# Signal_Relay_Switch.net
KiCad netlist of a schematic drawn in EasyEDA Pro
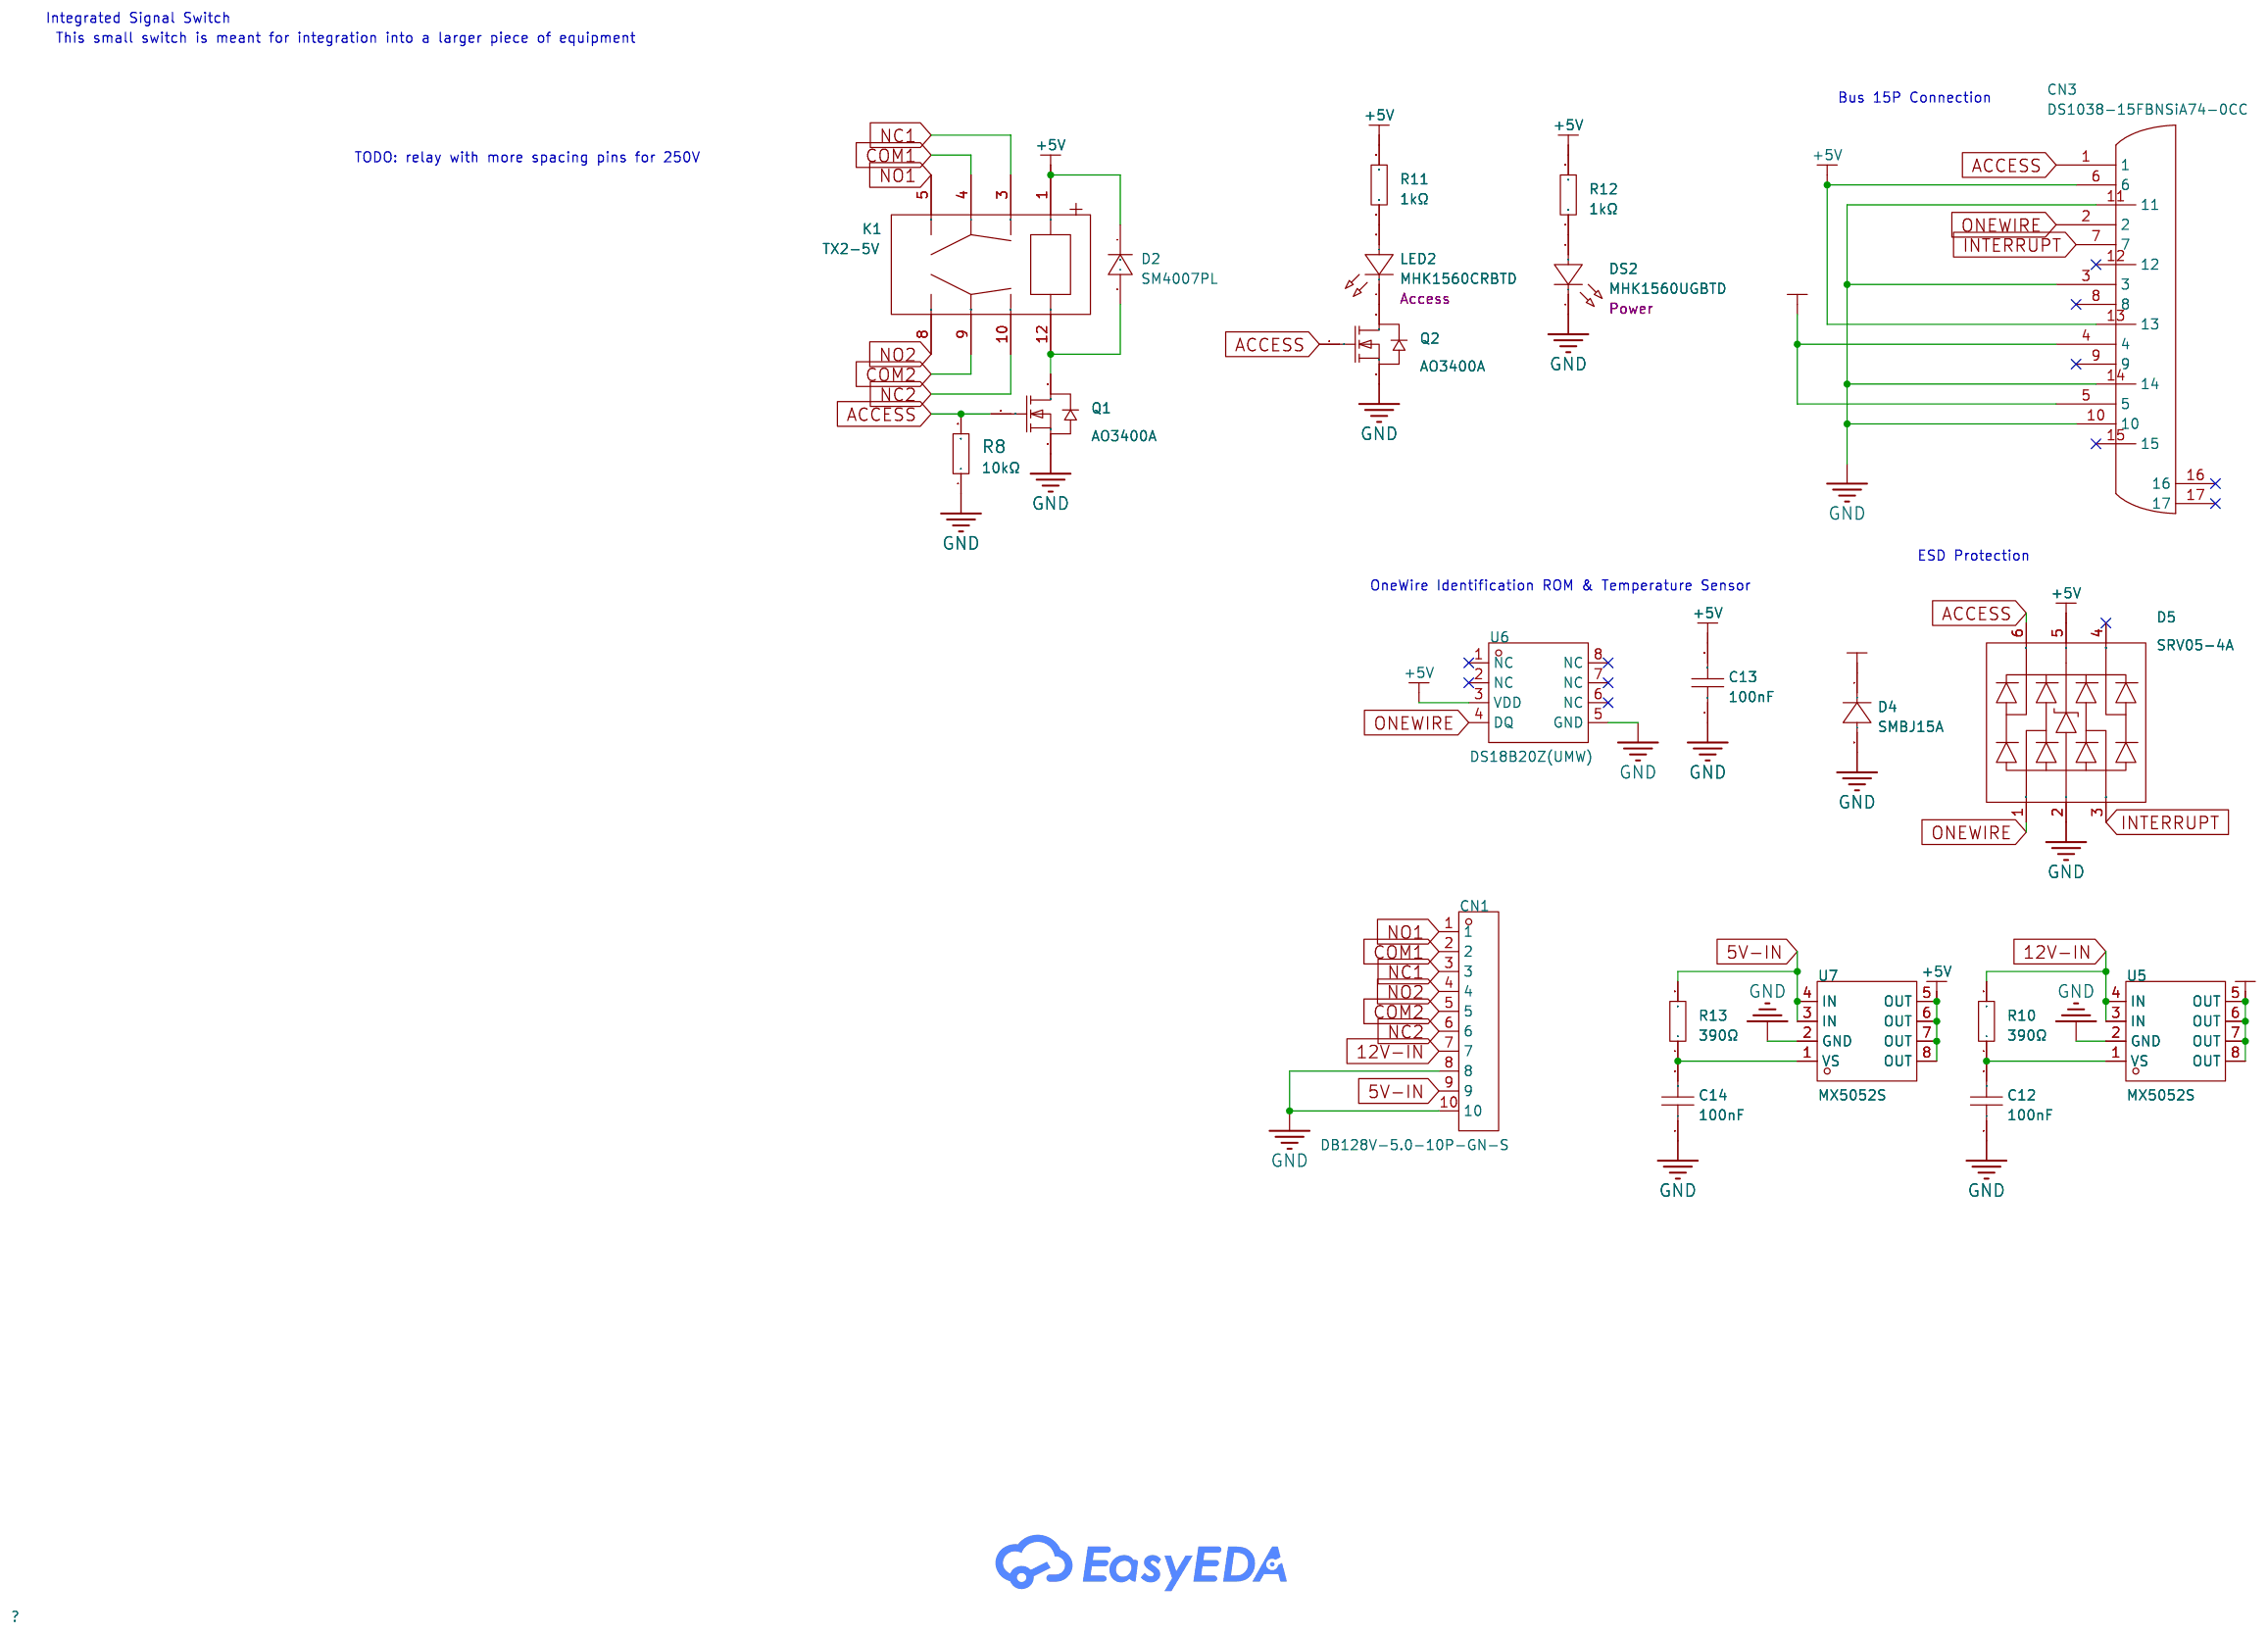
[diagram p0: schematic sheet]

(export (version "E")
  (design (tool "Eeschema 10.0.6"))
  (components
    (comp (ref "C12")
      (value "100nF")
      (footprint "easyedapro:C0603")
      (description "Capacitance:100nF Tolerance:±10% Tolerance:±10% Voltage Rating:50V Temperature Coefficient:X7R")
      (fields
        (field (name "Manufacturer Part") "CC0603KRX7R9BB104")
        (field (name "Manufacturer") "YAGEO(国巨)")
      )
      (libsource (lib "easyedapro") (part "CC0603KRX7R9BB104"))
    )
    (comp (ref "C13")
      (value "100nF")
      (footprint "easyedapro:C0603")
      (description "Capacitance:100nF Tolerance:±10% Tolerance:±10% Voltage Rating:50V Temperature Coefficient:X7R")
      (fields
        (field (name "Manufacturer Part") "CC0603KRX7R9BB104")
        (field (name "Manufacturer") "YAGEO(国巨)")
      )
      (libsource (lib "easyedapro") (part "CC0603KRX7R9BB104"))
    )
    (comp (ref "C14")
      (value "100nF")
      (footprint "easyedapro:C0603")
      (description "Capacitance:100nF Tolerance:±10% Tolerance:±10% Voltage Rating:50V Temperature Coefficient:X7R")
      (fields
        (field (name "Manufacturer Part") "CC0603KRX7R9BB104")
        (field (name "Manufacturer") "YAGEO(国巨)")
      )
      (libsource (lib "easyedapro") (part "CC0603KRX7R9BB104"))
    )
    (comp (ref "CN1")
      (value "DB128V-5.0-10P-GN-S")
      (footprint "easyedapro:CONN-TH_DB128V-5.0-10P-GN-S")
      (fields (field (name "Manufacturer") "DORABO(地博电气)"))
      (libsource (lib "easyedapro") (part "DB128V-5.0-10P-GN-S"))
    )
    (comp (ref "CN3")
      (value "DS1038-15FBNSiA74-0CC")
      (footprint "easyedapro:DSUB-TH_DS1038-15FBNSIA74-0CC")
      (fields (field (name "Manufacturer") "CONNFLY"))
      (libsource (lib "easyedapro") (part "DS1038-15FBNSIA74-0CC"))
    )
    (comp (ref "D2")
      (value "SM4007PL")
      (footprint "easyedapro:SOD-123F_L2.8-W1.8-LS3.7-RD")
      (fields (field (name "Manufacturer") "MDD(辰达半导体)"))
      (libsource (lib "easyedapro") (part "SM4007PL"))
    )
    (comp (ref "D4")
      (value "SMBJ15A")
      (footprint "easyedapro:SMB_L4.3-W3.6-LS5.3-RD")
      (fields (field (name "Manufacturer") "R+O(宏嘉诚)"))
      (libsource (lib "easyedapro") (part "SMBJ15A_C19077569"))
    )
    (comp (ref "D5")
      (value "SRV05-4A")
      (footprint "easyedapro:SOT-23-6_L2.9-W1.6-P0.95-LS2.9-BL")
      (fields (field (name "Manufacturer") "R+O(宏嘉诚)"))
      (libsource (lib "easyedapro") (part "SRV05-4A_C20615829"))
    )
    (comp (ref "DS2")
      (value "MHK1560UGBTD")
      (footprint "easyedapro:LED-TH_MHK1560UGBTD")
      (fields (field (name "Manufacturer") "MEIHUA(美华)") (field (name "Note") "Power"))
      (libsource (lib "easyedapro") (part "MHK1560UGBTD"))
    )
    (comp (ref "K1")
      (value "TX2-5V")
      (footprint "easyedapro:RELAY-TH_TX2-3V")
      (fields (field (name "Manufacturer") "PANASONIC(松下)"))
      (libsource (lib "easyedapro") (part "TX2-5V"))
    )
    (comp (ref "LED2")
      (value "MHK1560CRBTD")
      (footprint "easyedapro:LED-TH_L12.2-W6.0-P2.54")
      (fields (field (name "Manufacturer") "MEIHUA(美华)") (field (name "Note") "Access"))
      (libsource (lib "easyedapro") (part "MHK1560CRBTD"))
    )
    (comp (ref "Q1")
      (value "AO3400A")
      (footprint "easyedapro:SOT-23-3_L2.9-W1.3-P1.90-LS2.4-BR")
      (fields (field (name "Manufacturer") "AOS"))
      (libsource (lib "easyedapro") (part "AO3400A"))
    )
    (comp (ref "Q2")
      (value "AO3400A")
      (footprint "easyedapro:SOT-23-3_L2.9-W1.3-P1.90-LS2.4-BR")
      (fields (field (name "Manufacturer") "AOS"))
      (libsource (lib "easyedapro") (part "AO3400A"))
    )
    (comp (ref "R8")
      (value "10kΩ")
      (footprint "easyedapro:R0603")
      (fields
        (field (name "Manufacturer Part") "0603WAF1002T5E")
        (field (name "Manufacturer") "UNI-ROYAL(厚声)")
      )
      (libsource (lib "easyedapro") (part "0603WAF1002T5E"))
    )
    (comp (ref "R10")
      (value "390Ω")
      (footprint "easyedapro:R0805")
      (fields
        (field (name "Manufacturer Part") "0805W8F3900T5E")
        (field (name "Manufacturer") "UNI-ROYAL(厚声)")
      )
      (libsource (lib "easyedapro") (part "0805W8F3900T5E"))
    )
    (comp (ref "R11")
      (value "1kΩ")
      (footprint "easyedapro:R0603")
      (fields
        (field (name "Manufacturer Part") "0603WAF1001T5E")
        (field (name "Manufacturer") "UNI-ROYAL(厚声)")
      )
      (libsource (lib "easyedapro") (part "0603WAF1001T5E"))
    )
    (comp (ref "R12")
      (value "1kΩ")
      (footprint "easyedapro:R0603")
      (fields
        (field (name "Manufacturer Part") "0603WAF1001T5E")
        (field (name "Manufacturer") "UNI-ROYAL(厚声)")
      )
      (libsource (lib "easyedapro") (part "0603WAF1001T5E"))
    )
    (comp (ref "R13")
      (value "390Ω")
      (footprint "easyedapro:R0805")
      (fields
        (field (name "Manufacturer Part") "0805W8F3900T5E")
        (field (name "Manufacturer") "UNI-ROYAL(厚声)")
      )
      (libsource (lib "easyedapro") (part "0805W8F3900T5E"))
    )
    (comp (ref "U5")
      (value "MX5052S")
      (footprint "easyedapro:SOP-8_L4.9-W3.9-P1.27-LS6.0-BL")
      (fields (field (name "Manufacturer") "Wuxi Maxinmicro(无锡明芯微)"))
      (libsource (lib "easyedapro") (part "MX5052S"))
    )
    (comp (ref "U6")
      (value "DS18B20Z(UMW)")
      (footprint "easyedapro:SOP-8_L4.9-W3.9-P1.27-LS6.0-BL")
      (fields (field (name "Manufacturer") "UMW(友台半导体)"))
      (libsource (lib "easyedapro") (part "DS18B20Z"))
    )
    (comp (ref "U7")
      (value "MX5052S")
      (footprint "easyedapro:SOP-8_L4.9-W3.9-P1.27-LS6.0-BL")
      (fields (field (name "Manufacturer") "Wuxi Maxinmicro(无锡明芯微)"))
      (libsource (lib "easyedapro") (part "MX5052S"))
    )
  )
  (nets
    (net (code "1") (name "+5V") (class "Default")
      (node (ref "C13") (pin "2") (pinfunction "2_2") (pintype "unspecified"))
      (node (ref "CN3") (pin "13") (pinfunction "13_13") (pintype "unspecified"))
      (node (ref "CN3") (pin "6") (pinfunction "6_6") (pintype "unspecified"))
      (node (ref "D2") (pin "1") (pinfunction "C_1") (pintype "unspecified"))
      (node (ref "D5") (pin "5") (pinfunction "VP_5") (pintype "unspecified"))
      (node (ref "K1") (pin "1") (pinfunction "1_1") (pintype "unspecified"))
      (node (ref "R11") (pin "2") (pinfunction "2_2") (pintype "input"))
      (node (ref "R12") (pin "2") (pinfunction "2_2") (pintype "input"))
      (node (ref "U6") (pin "3") (pinfunction "VDD_3") (pintype "unspecified"))
      (node (ref "U7") (pin "5") (pinfunction "OUT_5") (pintype "unspecified"))
      (node (ref "U7") (pin "6") (pinfunction "OUT_6") (pintype "unspecified"))
      (node (ref "U7") (pin "7") (pinfunction "OUT_7") (pintype "unspecified"))
      (node (ref "U7") (pin "8") (pinfunction "OUT_8") (pintype "unspecified"))
    )
    (net (code "2") (name "+12V") (class "Default")
      (node (ref "CN3") (pin "4") (pinfunction "4_4") (pintype "unspecified"))
      (node (ref "CN3") (pin "5") (pinfunction "5_5") (pintype "unspecified"))
      (node (ref "D4") (pin "1") (pinfunction "K_1") (pintype "unspecified"))
      (node (ref "U5") (pin "5") (pinfunction "OUT_5") (pintype "unspecified"))
      (node (ref "U5") (pin "6") (pinfunction "OUT_6") (pintype "unspecified"))
      (node (ref "U5") (pin "7") (pinfunction "OUT_7") (pintype "unspecified"))
      (node (ref "U5") (pin "8") (pinfunction "OUT_8") (pintype "unspecified"))
    )
    (net (code "3") (name "5V-IN") (class "Default")
      (node (ref "CN1") (pin "9") (pinfunction "9_9") (pintype "unspecified"))
      (node (ref "R13") (pin "2") (pinfunction "2_2") (pintype "input"))
      (node (ref "U7") (pin "3") (pinfunction "IN_3") (pintype "unspecified"))
      (node (ref "U7") (pin "4") (pinfunction "IN_4") (pintype "unspecified"))
    )
    (net (code "4") (name "12V-IN") (class "Default")
      (node (ref "CN1") (pin "7") (pinfunction "7_7") (pintype "unspecified"))
      (node (ref "R10") (pin "2") (pinfunction "2_2") (pintype "input"))
      (node (ref "U5") (pin "3") (pinfunction "IN_3") (pintype "unspecified"))
      (node (ref "U5") (pin "4") (pinfunction "IN_4") (pintype "unspecified"))
    )
    (net (code "5") (name "ACCESS") (class "Default")
      (node (ref "CN3") (pin "1") (pinfunction "1_1") (pintype "unspecified"))
      (node (ref "D5") (pin "6") (pinfunction "I/O_6") (pintype "unspecified"))
      (node (ref "Q1") (pin "1") (pinfunction "G_1") (pintype "unspecified"))
      (node (ref "Q2") (pin "1") (pinfunction "G_1") (pintype "unspecified"))
      (node (ref "R8") (pin "2") (pinfunction "2_2") (pintype "input"))
    )
    (net (code "6") (name "COM1") (class "Default")
      (node (ref "CN1") (pin "2") (pinfunction "2_2") (pintype "unspecified"))
      (node (ref "K1") (pin "4") (pinfunction "4_4") (pintype "unspecified"))
    )
    (net (code "7") (name "COM2") (class "Default")
      (node (ref "CN1") (pin "5") (pinfunction "5_5") (pintype "unspecified"))
      (node (ref "K1") (pin "9") (pinfunction "9_9") (pintype "unspecified"))
    )
    (net (code "8") (name "GND") (class "Default")
      (node (ref "C12") (pin "1") (pinfunction "1_1") (pintype "unspecified"))
      (node (ref "C13") (pin "1") (pinfunction "1_1") (pintype "unspecified"))
      (node (ref "C14") (pin "1") (pinfunction "1_1") (pintype "unspecified"))
      (node (ref "CN1") (pin "10") (pinfunction "10_10") (pintype "unspecified"))
      (node (ref "CN1") (pin "8") (pinfunction "8_8") (pintype "unspecified"))
      (node (ref "CN3") (pin "10") (pinfunction "10_10") (pintype "unspecified"))
      (node (ref "CN3") (pin "11") (pinfunction "11_11") (pintype "unspecified"))
      (node (ref "CN3") (pin "14") (pinfunction "14_14") (pintype "unspecified"))
      (node (ref "CN3") (pin "3") (pinfunction "3_3") (pintype "unspecified"))
      (node (ref "D4") (pin "2") (pinfunction "A_2") (pintype "unspecified"))
      (node (ref "D5") (pin "2") (pinfunction "VN_2") (pintype "unspecified"))
      (node (ref "DS2") (pin "1") (pinfunction "K_1") (pintype "unspecified"))
      (node (ref "Q1") (pin "2") (pinfunction "S_2") (pintype "unspecified"))
      (node (ref "Q2") (pin "2") (pinfunction "S_2") (pintype "unspecified"))
      (node (ref "R8") (pin "1") (pinfunction "1_1") (pintype "input"))
      (node (ref "U5") (pin "2") (pinfunction "GND_2") (pintype "unspecified"))
      (node (ref "U6") (pin "5") (pinfunction "GND_5") (pintype "unspecified"))
      (node (ref "U7") (pin "2") (pinfunction "GND_2") (pintype "unspecified"))
    )
    (net (code "9") (name "INTERRUPT") (class "Default")
      (node (ref "CN3") (pin "7") (pinfunction "7_7") (pintype "unspecified"))
      (node (ref "D5") (pin "3") (pinfunction "I/O_3") (pintype "unspecified"))
    )
    (net (code "10") (name "NC1") (class "Default")
      (node (ref "CN1") (pin "3") (pinfunction "3_3") (pintype "unspecified"))
      (node (ref "K1") (pin "3") (pinfunction "3_3") (pintype "unspecified"))
    )
    (net (code "11") (name "NC2") (class "Default")
      (node (ref "CN1") (pin "6") (pinfunction "6_6") (pintype "unspecified"))
      (node (ref "K1") (pin "10") (pinfunction "10_10") (pintype "unspecified"))
    )
    (net (code "12") (name "NO1") (class "Default")
      (node (ref "CN1") (pin "1") (pinfunction "1_1") (pintype "unspecified"))
      (node (ref "K1") (pin "5") (pinfunction "5_5") (pintype "unspecified"))
    )
    (net (code "13") (name "NO2") (class "Default")
      (node (ref "CN1") (pin "4") (pinfunction "4_4") (pintype "unspecified"))
      (node (ref "K1") (pin "8") (pinfunction "8_8") (pintype "unspecified"))
    )
    (net (code "14") (name "Net-(D2-A)") (class "Default")
      (node (ref "D2") (pin "2") (pinfunction "A_2") (pintype "unspecified"))
      (node (ref "K1") (pin "12") (pinfunction "12_12") (pintype "unspecified"))
      (node (ref "Q1") (pin "3") (pinfunction "D_3") (pintype "unspecified"))
    )
    (net (code "15") (name "Net-(DS2-A)") (class "Default")
      (node (ref "DS2") (pin "2") (pinfunction "A_2") (pintype "unspecified"))
      (node (ref "R12") (pin "1") (pinfunction "1_1") (pintype "input"))
    )
    (net (code "16") (name "Net-(LED2-A)") (class "Default")
      (node (ref "LED2") (pin "2") (pinfunction "A_2") (pintype "unspecified"))
      (node (ref "R11") (pin "1") (pinfunction "1_1") (pintype "input"))
    )
    (net (code "17") (name "Net-(LED2-K)") (class "Default")
      (node (ref "LED2") (pin "1") (pinfunction "K_1") (pintype "unspecified"))
      (node (ref "Q2") (pin "3") (pinfunction "D_3") (pintype "unspecified"))
    )
    (net (code "18") (name "Net-(U5-VS)") (class "Default")
      (node (ref "C12") (pin "2") (pinfunction "2_2") (pintype "unspecified"))
      (node (ref "R10") (pin "1") (pinfunction "1_1") (pintype "input"))
      (node (ref "U5") (pin "1") (pinfunction "VS_1") (pintype "unspecified"))
    )
    (net (code "19") (name "Net-(U7-VS)") (class "Default")
      (node (ref "C14") (pin "2") (pinfunction "2_2") (pintype "unspecified"))
      (node (ref "R13") (pin "1") (pinfunction "1_1") (pintype "input"))
      (node (ref "U7") (pin "1") (pinfunction "VS_1") (pintype "unspecified"))
    )
    (net (code "20") (name "ONEWIRE") (class "Default")
      (node (ref "CN3") (pin "2") (pinfunction "2_2") (pintype "unspecified"))
      (node (ref "D5") (pin "1") (pinfunction "I/O_1") (pintype "unspecified"))
      (node (ref "U6") (pin "4") (pinfunction "DQ_4") (pintype "unspecified"))
    )
    (net (code "21") (name "unconnected-(CN3-Pad8)") (class "Default")
      (node (ref "CN3") (pin "8") (pinfunction "8_8") (pintype "unspecified+no_connect"))
    )
    (net (code "22") (name "unconnected-(CN3-Pad9)") (class "Default")
      (node (ref "CN3") (pin "9") (pinfunction "9_9") (pintype "unspecified+no_connect"))
    )
    (net (code "23") (name "unconnected-(CN3-Pad12)") (class "Default")
      (node (ref "CN3") (pin "12") (pinfunction "12_12") (pintype "unspecified+no_connect"))
    )
    (net (code "24") (name "unconnected-(CN3-Pad15)") (class "Default")
      (node (ref "CN3") (pin "15") (pinfunction "15_15") (pintype "unspecified+no_connect"))
    )
    (net (code "25") (name "unconnected-(CN3-Pad16)") (class "Default")
      (node (ref "CN3") (pin "16") (pinfunction "16_16") (pintype "unspecified+no_connect"))
    )
    (net (code "26") (name "unconnected-(CN3-Pad17)") (class "Default")
      (node (ref "CN3") (pin "17") (pinfunction "17_17") (pintype "unspecified+no_connect"))
    )
    (net (code "27") (name "unconnected-(D5-I{slash}O-Pad4)") (class "Default")
      (node (ref "D5") (pin "4") (pinfunction "I/O_4") (pintype "unspecified+no_connect"))
    )
    (net (code "28") (name "unconnected-(U6-NC-Pad1)") (class "Default")
      (node (ref "U6") (pin "1") (pinfunction "NC_1") (pintype "unspecified+no_connect"))
    )
    (net (code "29") (name "unconnected-(U6-NC-Pad2)") (class "Default")
      (node (ref "U6") (pin "2") (pinfunction "NC_2") (pintype "unspecified+no_connect"))
    )
    (net (code "30") (name "unconnected-(U6-NC-Pad6)") (class "Default")
      (node (ref "U6") (pin "6") (pinfunction "NC_6") (pintype "unspecified+no_connect"))
    )
    (net (code "31") (name "unconnected-(U6-NC-Pad7)") (class "Default")
      (node (ref "U6") (pin "7") (pinfunction "NC_7") (pintype "unspecified+no_connect"))
    )
    (net (code "32") (name "unconnected-(U6-NC-Pad8)") (class "Default")
      (node (ref "U6") (pin "8") (pinfunction "NC_8") (pintype "unspecified+no_connect"))
    )
  )
)
